# 02_ESP12_CORE.net
KiCad netlist of a schematic drawn in Altium Designer
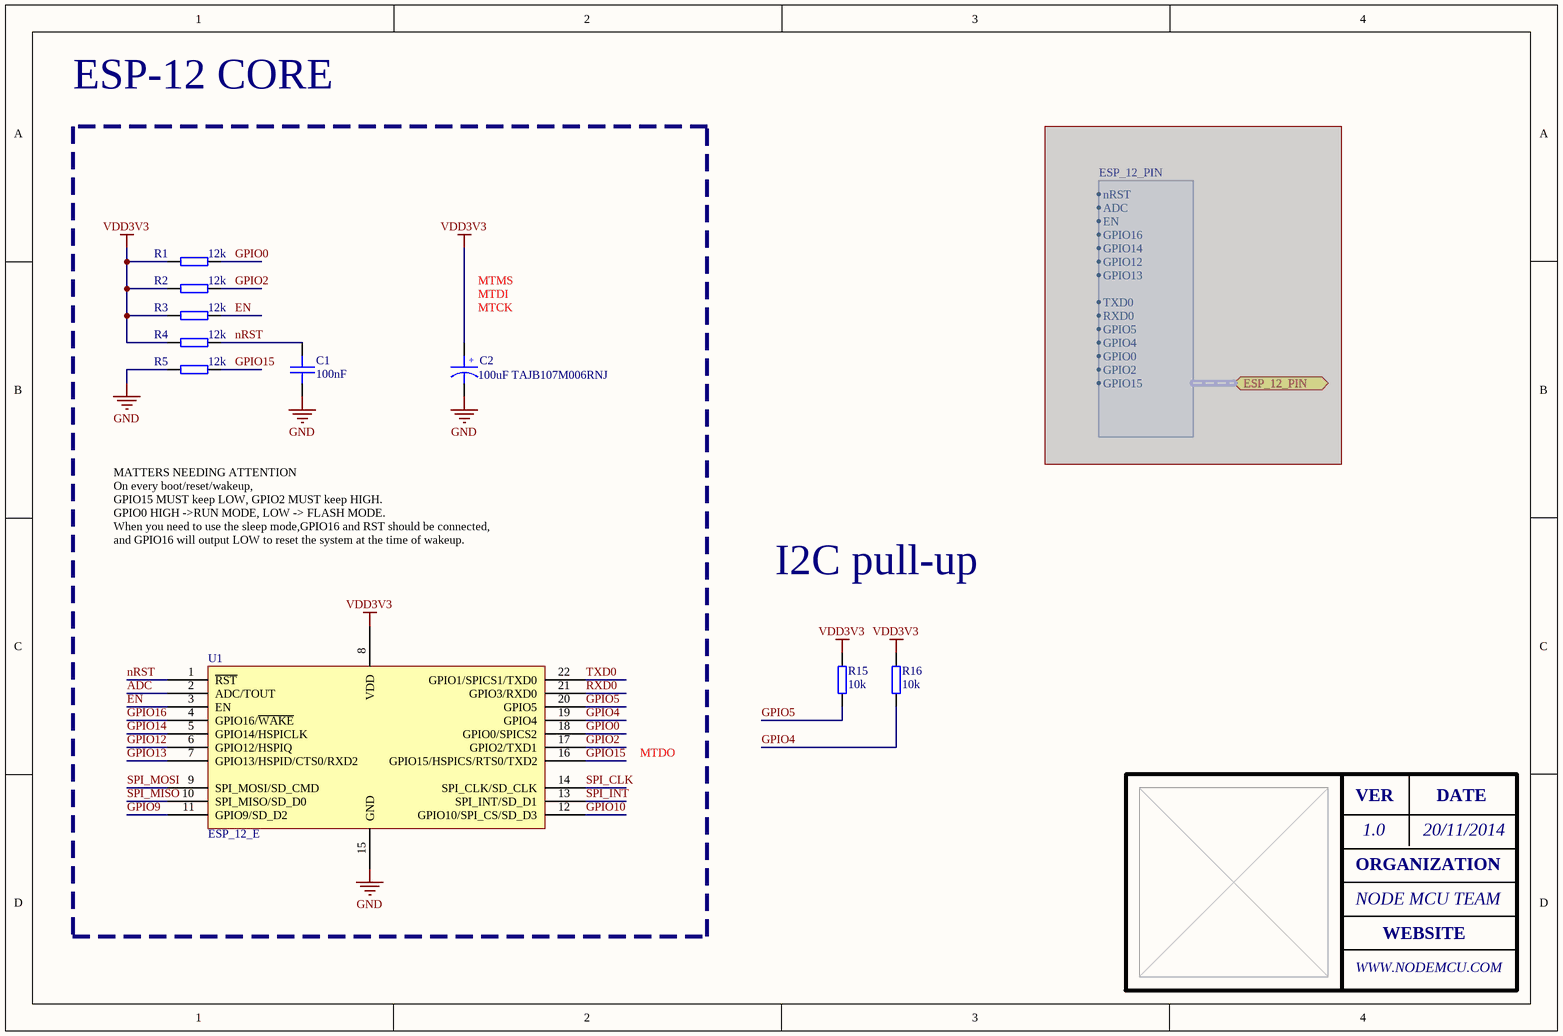
[diagram p0: 02_ESP12_CORE.SchDoc]

(export (version "E")
  (design (tool "Eeschema 10.0.6"))
  (components
    (comp (ref "C1")
      (value "100nF")
      (footprint "SMT_C_0402")
      (description "Surface mount capacitor 0402")
      (libsource (lib "Vowstar_Basic_Device") (part "SMT_C_0402"))
    )
    (comp (ref "C2")
      (value "100uF TAJB107M006RNJ")
      (footprint "SMT_C_Tantalum_B")
      (description "Capacitor, SM Tantalum; Body 3.5 x 2.8 mm (LxW typ)")
      (libsource (lib "Vowstar_Basic_Device") (part "SMT_C_Tantalum_B"))
    )
    (comp (ref "R1")
      (value "12k")
      (footprint "SMT_R_0402")
      (description "Surface mount resistor 0402")
      (libsource (lib "Vowstar_Basic_Device") (part "SMT_R_0402"))
    )
    (comp (ref "R2")
      (value "12k")
      (footprint "SMT_R_0402")
      (description "Surface mount resistor 0402")
      (libsource (lib "Vowstar_Basic_Device") (part "SMT_R_0402"))
    )
    (comp (ref "R3")
      (value "12k")
      (footprint "SMT_R_0402")
      (description "Surface mount resistor 0402")
      (libsource (lib "Vowstar_Basic_Device") (part "SMT_R_0402"))
    )
    (comp (ref "R4")
      (value "12k")
      (footprint "SMT_R_0402")
      (description "Surface mount resistor 0402")
      (libsource (lib "Vowstar_Basic_Device") (part "SMT_R_0402"))
    )
    (comp (ref "R5")
      (value "12k")
      (footprint "SMT_R_0402")
      (description "Surface mount resistor 0402")
      (libsource (lib "Vowstar_Basic_Device") (part "SMT_R_0402"))
    )
    (comp (ref "R15")
      (value "10k")
      (footprint "SMT_R_0402")
      (description "Surface mount resistor 0402")
      (libsource (lib "Vowstar_Basic_Device") (part "SMT_R_0402"))
    )
    (comp (ref "R16")
      (value "10k")
      (footprint "SMT_R_0402")
      (description "Surface mount resistor 0402")
      (libsource (lib "Vowstar_Basic_Device") (part "SMT_R_0402"))
    )
    (comp (ref "U1")
      (value "ESP_12_E")
      (footprint "ESP_12_E_L")
      (description "ESP-12 Wi-Fi Module by AI-Thinker")
      (libsource (lib "Vowstar_Module") (part "ESP_12_E"))
    )
  )
  (nets
    (net (code "2") (name "/ADC") (class "Default")
      (node (ref "U1") (pin "2") (pinfunction "ADC/TOUT_2") (pintype "passive"))
    )
    (net (code "3") (name "/EN") (class "Default")
      (node (ref "R3") (pin "2") (pinfunction "2_2") (pintype "passive"))
      (node (ref "U1") (pin "3") (pinfunction "EN_3") (pintype "passive"))
    )
    (net (code "4") (name "/GPIO0") (class "Default")
      (node (ref "R1") (pin "2") (pinfunction "2_2") (pintype "passive"))
      (node (ref "U1") (pin "18") (pinfunction "GPIO0/SPICS2_18") (pintype "passive"))
    )
    (net (code "5") (name "/GPIO2") (class "Default")
      (node (ref "R2") (pin "2") (pinfunction "2_2") (pintype "passive"))
      (node (ref "U1") (pin "17") (pinfunction "GPIO2/TXD1_17") (pintype "passive"))
    )
    (net (code "6") (name "/GPIO4") (class "Default")
      (node (ref "R16") (pin "1") (pinfunction "1_1") (pintype "passive"))
      (node (ref "U1") (pin "19") (pinfunction "GPIO4_19") (pintype "passive"))
    )
    (net (code "7") (name "/GPIO5") (class "Default")
      (node (ref "R15") (pin "1") (pinfunction "1_1") (pintype "passive"))
      (node (ref "U1") (pin "20") (pinfunction "GPIO5_20") (pintype "passive"))
    )
    (net (code "8") (name "/GPIO9") (class "Default")
      (node (ref "U1") (pin "11") (pinfunction "GPIO9/SD_D2_11") (pintype "passive"))
    )
    (net (code "9") (name "/GPIO10") (class "Default")
      (node (ref "U1") (pin "12") (pinfunction "GPIO10/SPI_CS/SD_D3_12") (pintype "passive"))
    )
    (net (code "10") (name "/GPIO12") (class "Default")
      (node (ref "U1") (pin "6") (pinfunction "GPIO12/HSPIQ_6") (pintype "passive"))
    )
    (net (code "11") (name "/GPIO13") (class "Default")
      (node (ref "U1") (pin "7") (pinfunction "GPIO13/HSPID/CTS0/RXD2_7") (pintype "passive"))
    )
    (net (code "12") (name "/GPIO14") (class "Default")
      (node (ref "U1") (pin "5") (pinfunction "GPIO14/HSPICLK_5") (pintype "passive"))
    )
    (net (code "13") (name "/GPIO15") (class "Default")
      (node (ref "R5") (pin "2") (pinfunction "2_2") (pintype "passive"))
      (node (ref "U1") (pin "16") (pinfunction "GPIO15/HSPICS/RTS0/TXD2_16") (pintype "passive"))
    )
    (net (code "14") (name "/GPIO16") (class "Default")
      (node (ref "U1") (pin "4") (pinfunction "GPIO16/~{WAKE}_4") (pintype "passive"))
    )
    (net (code "15") (name "/RXD0") (class "Default")
      (node (ref "U1") (pin "21") (pinfunction "GPIO3/RXD0_21") (pintype "passive"))
    )
    (net (code "16") (name "/SPI_CLK") (class "Default")
      (node (ref "U1") (pin "14") (pinfunction "SPI_CLK/SD_CLK_14") (pintype "passive"))
    )
    (net (code "17") (name "/SPI_INT") (class "Default")
      (node (ref "U1") (pin "13") (pinfunction "SPI_INT/SD_D1_13") (pintype "passive"))
    )
    (net (code "18") (name "/SPI_MISO") (class "Default")
      (node (ref "U1") (pin "10") (pinfunction "SPI_MISO/SD_D0_10") (pintype "passive"))
    )
    (net (code "19") (name "/SPI_MOSI") (class "Default")
      (node (ref "U1") (pin "9") (pinfunction "SPI_MOSI/SD_CMD_9") (pintype "passive"))
    )
    (net (code "20") (name "/TXD0") (class "Default")
      (node (ref "U1") (pin "22") (pinfunction "GPIO1/SPICS1/TXD0_22") (pintype "passive"))
    )
    (net (code "21") (name "/nRST") (class "Default")
      (node (ref "C1") (pin "1") (pinfunction "1_1") (pintype "passive"))
      (node (ref "R4") (pin "2") (pinfunction "2_2") (pintype "passive"))
      (node (ref "U1") (pin "1") (pinfunction "~{RST}_1") (pintype "passive"))
    )
    (net (code "23") (name "GND") (class "Default")
      (node (ref "C1") (pin "2") (pinfunction "2_2") (pintype "passive"))
      (node (ref "C2") (pin "2") (pinfunction "2_2") (pintype "passive"))
      (node (ref "R5") (pin "1") (pinfunction "1_1") (pintype "passive"))
      (node (ref "U1") (pin "15") (pinfunction "GND_15") (pintype "passive"))
    )
    (net (code "24") (name "VDD3V3") (class "Default")
      (node (ref "C2") (pin "1") (pinfunction "1_1") (pintype "passive"))
      (node (ref "R1") (pin "1") (pinfunction "1_1") (pintype "passive"))
      (node (ref "R15") (pin "2") (pinfunction "2_2") (pintype "passive"))
      (node (ref "R16") (pin "2") (pinfunction "2_2") (pintype "passive"))
      (node (ref "R2") (pin "1") (pinfunction "1_1") (pintype "passive"))
      (node (ref "R3") (pin "1") (pinfunction "1_1") (pintype "passive"))
      (node (ref "R4") (pin "1") (pinfunction "1_1") (pintype "passive"))
      (node (ref "U1") (pin "8") (pinfunction "VDD_8") (pintype "passive"))
    )
  )
)
